# HW2schematic.net
KiCad netlist of a schematic drawn in EAGLE
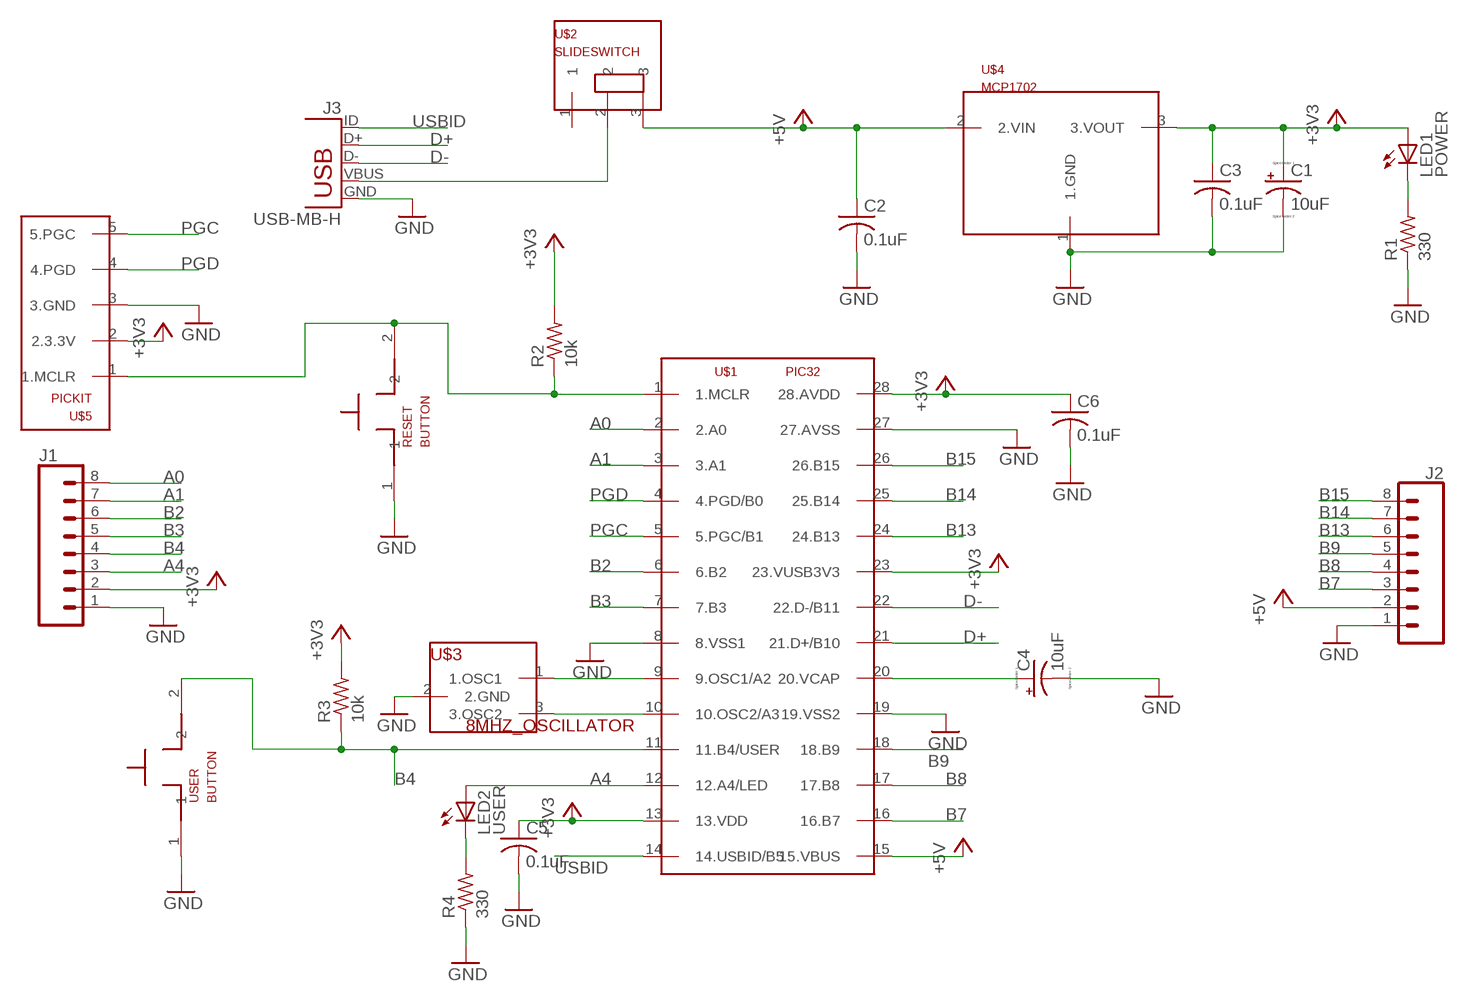
[diagram p0: schematic, sheet 1]

(export (version "E")
  (design (tool "Eeschema 10.0.6"))
  (components
    (comp (ref "C1")
      (value "10uF")
      (footprint "eagle-import:B45181B")
      (libsource (lib "eagle-import") (part "CPOL-USB45181B"))
    )
    (comp (ref "C2")
      (value "0.1uF")
      (footprint "eagle-import:C025-025X050")
      (libsource (lib "eagle-import") (part "C-US025-025X050"))
    )
    (comp (ref "C3")
      (value "0.1uF")
      (footprint "eagle-import:C025-025X050")
      (libsource (lib "eagle-import") (part "C-US025-025X050"))
    )
    (comp (ref "C4")
      (value "10uF")
      (footprint "eagle-import:B45181B")
      (libsource (lib "eagle-import") (part "CPOL-USB45181B"))
    )
    (comp (ref "C5")
      (value "0.1uF")
      (footprint "eagle-import:C025-025X050")
      (libsource (lib "eagle-import") (part "C-US025-025X050"))
    )
    (comp (ref "C6")
      (value "0.1uF")
      (footprint "eagle-import:C025-025X050")
      (libsource (lib "eagle-import") (part "C-US025-025X050"))
    )
    (comp (ref "J1")
      (value "CONN_08")
      (footprint "eagle-import:1X08_NO_SILK")
      (libsource (lib "eagle-import") (part "CONN_08"))
    )
    (comp (ref "J2")
      (value "CONN_08")
      (footprint "eagle-import:1X08_NO_SILK")
      (libsource (lib "eagle-import") (part "CONN_08"))
    )
    (comp (ref "J3")
      (value "USB-MB-H")
      (footprint "eagle-import:USB-MB-H")
      (libsource (lib "eagle-import") (part "USB-MB-H"))
    )
    (comp (ref "LED1")
      (value "POWER")
      (footprint "eagle-import:LED3MM")
      (libsource (lib "eagle-import") (part "LED3MM"))
    )
    (comp (ref "LED2")
      (value "USER")
      (footprint "eagle-import:LED3MM")
      (libsource (lib "eagle-import") (part "LED3MM"))
    )
    (comp (ref "R1")
      (value "330")
      (footprint "eagle-import:0207_10")
      (libsource (lib "eagle-import") (part "R-US_0207/10"))
    )
    (comp (ref "R2")
      (value "10k")
      (footprint "eagle-import:0207_10")
      (libsource (lib "eagle-import") (part "R-US_0207/10"))
    )
    (comp (ref "R3")
      (value "10k")
      (footprint "eagle-import:0207_10")
      (libsource (lib "eagle-import") (part "R-US_0207/10"))
    )
    (comp (ref "R4")
      (value "330")
      (footprint "eagle-import:0207_10")
      (libsource (lib "eagle-import") (part "R-US_0207/10"))
    )
    (comp (ref "RESET")
      (value "BUTTON")
      (footprint "eagle-import:BUTTON")
      (libsource (lib "eagle-import") (part "BUTTON"))
    )
    (comp (ref "U$1")
      (value "PIC32")
      (footprint "eagle-import:DIL28-3")
      (libsource (lib "eagle-import") (part "PIC32"))
    )
    (comp (ref "U$2")
      (value "SLIDESWITCH")
      (footprint "eagle-import:SLIDESWITCH")
      (libsource (lib "eagle-import") (part "SLIDESWITCH"))
    )
    (comp (ref "U$3")
      (value "8MHZ_OSCILLATOR")
      (footprint "eagle-import:1X03")
      (libsource (lib "eagle-import") (part "8MHZ_RESONATOR"))
    )
    (comp (ref "U$4")
      (value "MCP1702")
      (footprint "eagle-import:TO92")
      (libsource (lib "eagle-import") (part "MCP1702"))
    )
    (comp (ref "U$5")
      (value "PICKIT")
      (footprint "eagle-import:PICKIT")
      (libsource (lib "eagle-import") (part "PICKIT"))
    )
    (comp (ref "USER")
      (value "BUTTON")
      (footprint "eagle-import:BUTTON")
      (libsource (lib "eagle-import") (part "BUTTON"))
    )
  )
  (nets
    (net (code "1") (name "+3V3") (class "Default")
      (node (ref "C1") (pin "+") (pinfunction "+_+") (pintype "passive"))
      (node (ref "C3") (pin "1") (pinfunction "1_1") (pintype "passive"))
      (node (ref "C5") (pin "1") (pinfunction "1_1") (pintype "passive"))
      (node (ref "C6") (pin "1") (pinfunction "1_1") (pintype "passive"))
      (node (ref "J1") (pin "2") (pinfunction "2_2") (pintype "passive"))
      (node (ref "LED1") (pin "A") (pinfunction "A_A") (pintype "passive"))
      (node (ref "R2") (pin "2") (pinfunction "2_2") (pintype "passive"))
      (node (ref "R3") (pin "2") (pinfunction "2_2") (pintype "passive"))
      (node (ref "U$1") (pin "13") (pinfunction "13.VDD_13") (pintype "bidirectional"))
      (node (ref "U$1") (pin "23") (pinfunction "23.VUSB3V3_23") (pintype "bidirectional"))
      (node (ref "U$1") (pin "28") (pinfunction "28.AVDD_28") (pintype "bidirectional"))
      (node (ref "U$4") (pin "3") (pinfunction "3.VOUT_3") (pintype "bidirectional"))
      (node (ref "U$5") (pin "2") (pinfunction "2.3.3V_2") (pintype "bidirectional"))
    )
    (net (code "2") (name "+5V") (class "Default")
      (node (ref "C2") (pin "1") (pinfunction "1_1") (pintype "passive"))
      (node (ref "J2") (pin "2") (pinfunction "2_2") (pintype "passive"))
      (node (ref "U$1") (pin "15") (pinfunction "15.VBUS_15") (pintype "bidirectional"))
      (node (ref "U$2") (pin "3") (pinfunction "3_3") (pintype "bidirectional"))
      (node (ref "U$4") (pin "2") (pinfunction "2.VIN_2") (pintype "bidirectional"))
    )
    (net (code "3") (name "/A0") (class "Default")
      (node (ref "J1") (pin "8") (pinfunction "8_8") (pintype "passive"))
      (node (ref "U$1") (pin "2") (pinfunction "2.A0_2") (pintype "bidirectional"))
    )
    (net (code "4") (name "/A1") (class "Default")
      (node (ref "J1") (pin "7") (pinfunction "7_7") (pintype "passive"))
      (node (ref "U$1") (pin "3") (pinfunction "3.A1_3") (pintype "bidirectional"))
    )
    (net (code "5") (name "/A4") (class "Default")
      (node (ref "J1") (pin "3") (pinfunction "3_3") (pintype "passive"))
      (node (ref "LED2") (pin "A") (pinfunction "A_A") (pintype "passive"))
      (node (ref "U$1") (pin "12") (pinfunction "12.A4/LED_12") (pintype "bidirectional"))
    )
    (net (code "6") (name "/B2") (class "Default")
      (node (ref "J1") (pin "6") (pinfunction "6_6") (pintype "passive"))
      (node (ref "U$1") (pin "6") (pinfunction "6.B2_6") (pintype "bidirectional"))
    )
    (net (code "7") (name "/B3") (class "Default")
      (node (ref "J1") (pin "5") (pinfunction "5_5") (pintype "passive"))
      (node (ref "U$1") (pin "7") (pinfunction "7.B3_7") (pintype "bidirectional"))
    )
    (net (code "8") (name "/B4") (class "Default")
      (node (ref "J1") (pin "4") (pinfunction "4_4") (pintype "passive"))
      (node (ref "R3") (pin "1") (pinfunction "1_1") (pintype "passive"))
      (node (ref "U$1") (pin "11") (pinfunction "11.B4/USER_11") (pintype "bidirectional"))
      (node (ref "USER") (pin "2") (pinfunction "2_2") (pintype "bidirectional"))
    )
    (net (code "9") (name "/B7") (class "Default")
      (node (ref "J2") (pin "3") (pinfunction "3_3") (pintype "passive"))
      (node (ref "U$1") (pin "16") (pinfunction "16.B7_16") (pintype "bidirectional"))
    )
    (net (code "10") (name "/B8") (class "Default")
      (node (ref "J2") (pin "4") (pinfunction "4_4") (pintype "passive"))
      (node (ref "U$1") (pin "17") (pinfunction "17.B8_17") (pintype "bidirectional"))
    )
    (net (code "11") (name "/B9") (class "Default")
      (node (ref "J2") (pin "5") (pinfunction "5_5") (pintype "passive"))
      (node (ref "U$1") (pin "18") (pinfunction "18.B9_18") (pintype "bidirectional"))
    )
    (net (code "12") (name "/B13") (class "Default")
      (node (ref "J2") (pin "6") (pinfunction "6_6") (pintype "passive"))
      (node (ref "U$1") (pin "24") (pinfunction "24.B13_24") (pintype "bidirectional"))
    )
    (net (code "13") (name "/B14") (class "Default")
      (node (ref "J2") (pin "7") (pinfunction "7_7") (pintype "passive"))
      (node (ref "U$1") (pin "25") (pinfunction "25.B14_25") (pintype "bidirectional"))
    )
    (net (code "14") (name "/B15") (class "Default")
      (node (ref "J2") (pin "8") (pinfunction "8_8") (pintype "passive"))
      (node (ref "U$1") (pin "26") (pinfunction "26.B15_26") (pintype "bidirectional"))
    )
    (net (code "15") (name "/D+") (class "Default")
      (node (ref "J3") (pin "D+") (pinfunction "D+_D+") (pintype "bidirectional"))
      (node (ref "U$1") (pin "21") (pinfunction "21.D+/B10_21") (pintype "bidirectional"))
    )
    (net (code "16") (name "/D-") (class "Default")
      (node (ref "J3") (pin "D-") (pinfunction "D-_D-") (pintype "bidirectional"))
      (node (ref "U$1") (pin "22") (pinfunction "22.D-/B11_22") (pintype "bidirectional"))
    )
    (net (code "17") (name "/PGC") (class "Default")
      (node (ref "U$1") (pin "5") (pinfunction "5.PGC/B1_5") (pintype "bidirectional"))
      (node (ref "U$5") (pin "5") (pinfunction "5.PGC_5") (pintype "bidirectional"))
    )
    (net (code "18") (name "/PGD") (class "Default")
      (node (ref "U$1") (pin "4") (pinfunction "4.PGD/B0_4") (pintype "bidirectional"))
      (node (ref "U$5") (pin "4") (pinfunction "4.PGD_4") (pintype "bidirectional"))
    )
    (net (code "19") (name "/USBID") (class "Default")
      (node (ref "J3") (pin "ID") (pinfunction "D+1_ID") (pintype "bidirectional"))
      (node (ref "U$1") (pin "14") (pinfunction "14.USBID/B5_14") (pintype "bidirectional"))
    )
    (net (code "20") (name "GND") (class "Default")
      (node (ref "C1") (pin "-") (pinfunction "-_-") (pintype "passive"))
      (node (ref "C2") (pin "2") (pinfunction "2_2") (pintype "passive"))
      (node (ref "C3") (pin "2") (pinfunction "2_2") (pintype "passive"))
      (node (ref "C4") (pin "-") (pinfunction "-_-") (pintype "passive"))
      (node (ref "C5") (pin "2") (pinfunction "2_2") (pintype "passive"))
      (node (ref "C6") (pin "2") (pinfunction "2_2") (pintype "passive"))
      (node (ref "J1") (pin "1") (pinfunction "1_1") (pintype "passive"))
      (node (ref "J2") (pin "1") (pinfunction "1_1") (pintype "passive"))
      (node (ref "J3") (pin "GND") (pinfunction "GND_GND") (pintype "bidirectional"))
      (node (ref "R1") (pin "1") (pinfunction "1_1") (pintype "passive"))
      (node (ref "R4") (pin "1") (pinfunction "1_1") (pintype "passive"))
      (node (ref "RESET") (pin "1") (pinfunction "1_1") (pintype "bidirectional"))
      (node (ref "U$1") (pin "19") (pinfunction "19.VSS2_19") (pintype "bidirectional"))
      (node (ref "U$1") (pin "27") (pinfunction "27.AVSS_27") (pintype "bidirectional"))
      (node (ref "U$1") (pin "8") (pinfunction "8.VSS1_8") (pintype "bidirectional"))
      (node (ref "U$3") (pin "2") (pinfunction "2.GND_2") (pintype "bidirectional"))
      (node (ref "U$4") (pin "1") (pinfunction "1.GND_1") (pintype "bidirectional"))
      (node (ref "U$5") (pin "3") (pinfunction "3.GND_3") (pintype "bidirectional"))
      (node (ref "USER") (pin "1") (pinfunction "1_1") (pintype "bidirectional"))
    )
    (net (code "21") (name "Net-(J3-PadVBUS)") (class "Default")
      (node (ref "J3") (pin "VBUS") (pinfunction "VBUS_VBUS") (pintype "bidirectional"))
      (node (ref "U$2") (pin "2") (pinfunction "2_2") (pintype "bidirectional"))
    )
    (net (code "22") (name "Net-(LED1-C)") (class "Default")
      (node (ref "LED1") (pin "K") (pinfunction "C_K") (pintype "passive"))
      (node (ref "R1") (pin "2") (pinfunction "2_2") (pintype "passive"))
    )
    (net (code "23") (name "Net-(LED2-C)") (class "Default")
      (node (ref "LED2") (pin "K") (pinfunction "C_K") (pintype "passive"))
      (node (ref "R4") (pin "2") (pinfunction "2_2") (pintype "passive"))
    )
    (net (code "24") (name "Net-(U$1-1.MCLR)") (class "Default")
      (node (ref "R2") (pin "1") (pinfunction "1_1") (pintype "passive"))
      (node (ref "RESET") (pin "2") (pinfunction "2_2") (pintype "bidirectional"))
      (node (ref "U$1") (pin "1") (pinfunction "1.MCLR_1") (pintype "bidirectional"))
      (node (ref "U$5") (pin "1") (pinfunction "1.MCLR_1") (pintype "bidirectional"))
    )
    (net (code "25") (name "Net-(U$1-9.OSC1{slash}A2)") (class "Default")
      (node (ref "U$1") (pin "9") (pinfunction "9.OSC1/A2_9") (pintype "bidirectional"))
      (node (ref "U$3") (pin "1") (pinfunction "1.OSC1_1") (pintype "bidirectional"))
    )
    (net (code "26") (name "Net-(U$1-10.OSC2{slash}A3)") (class "Default")
      (node (ref "U$1") (pin "10") (pinfunction "10.OSC2/A3_10") (pintype "bidirectional"))
      (node (ref "U$3") (pin "3") (pinfunction "3.OSC2_3") (pintype "bidirectional"))
    )
    (net (code "27") (name "Net-(U$1-20.VCAP)") (class "Default")
      (node (ref "C4") (pin "+") (pinfunction "+_+") (pintype "passive"))
      (node (ref "U$1") (pin "20") (pinfunction "20.VCAP_20") (pintype "bidirectional"))
    )
    (net (code "28") (name "unconnected-(U$2-Pad1)") (class "Default")
      (node (ref "U$2") (pin "1") (pinfunction "1_1") (pintype "bidirectional"))
    )
  )
)
